# motherboard.net
KiCad netlist of a schematic drawn in EAGLE
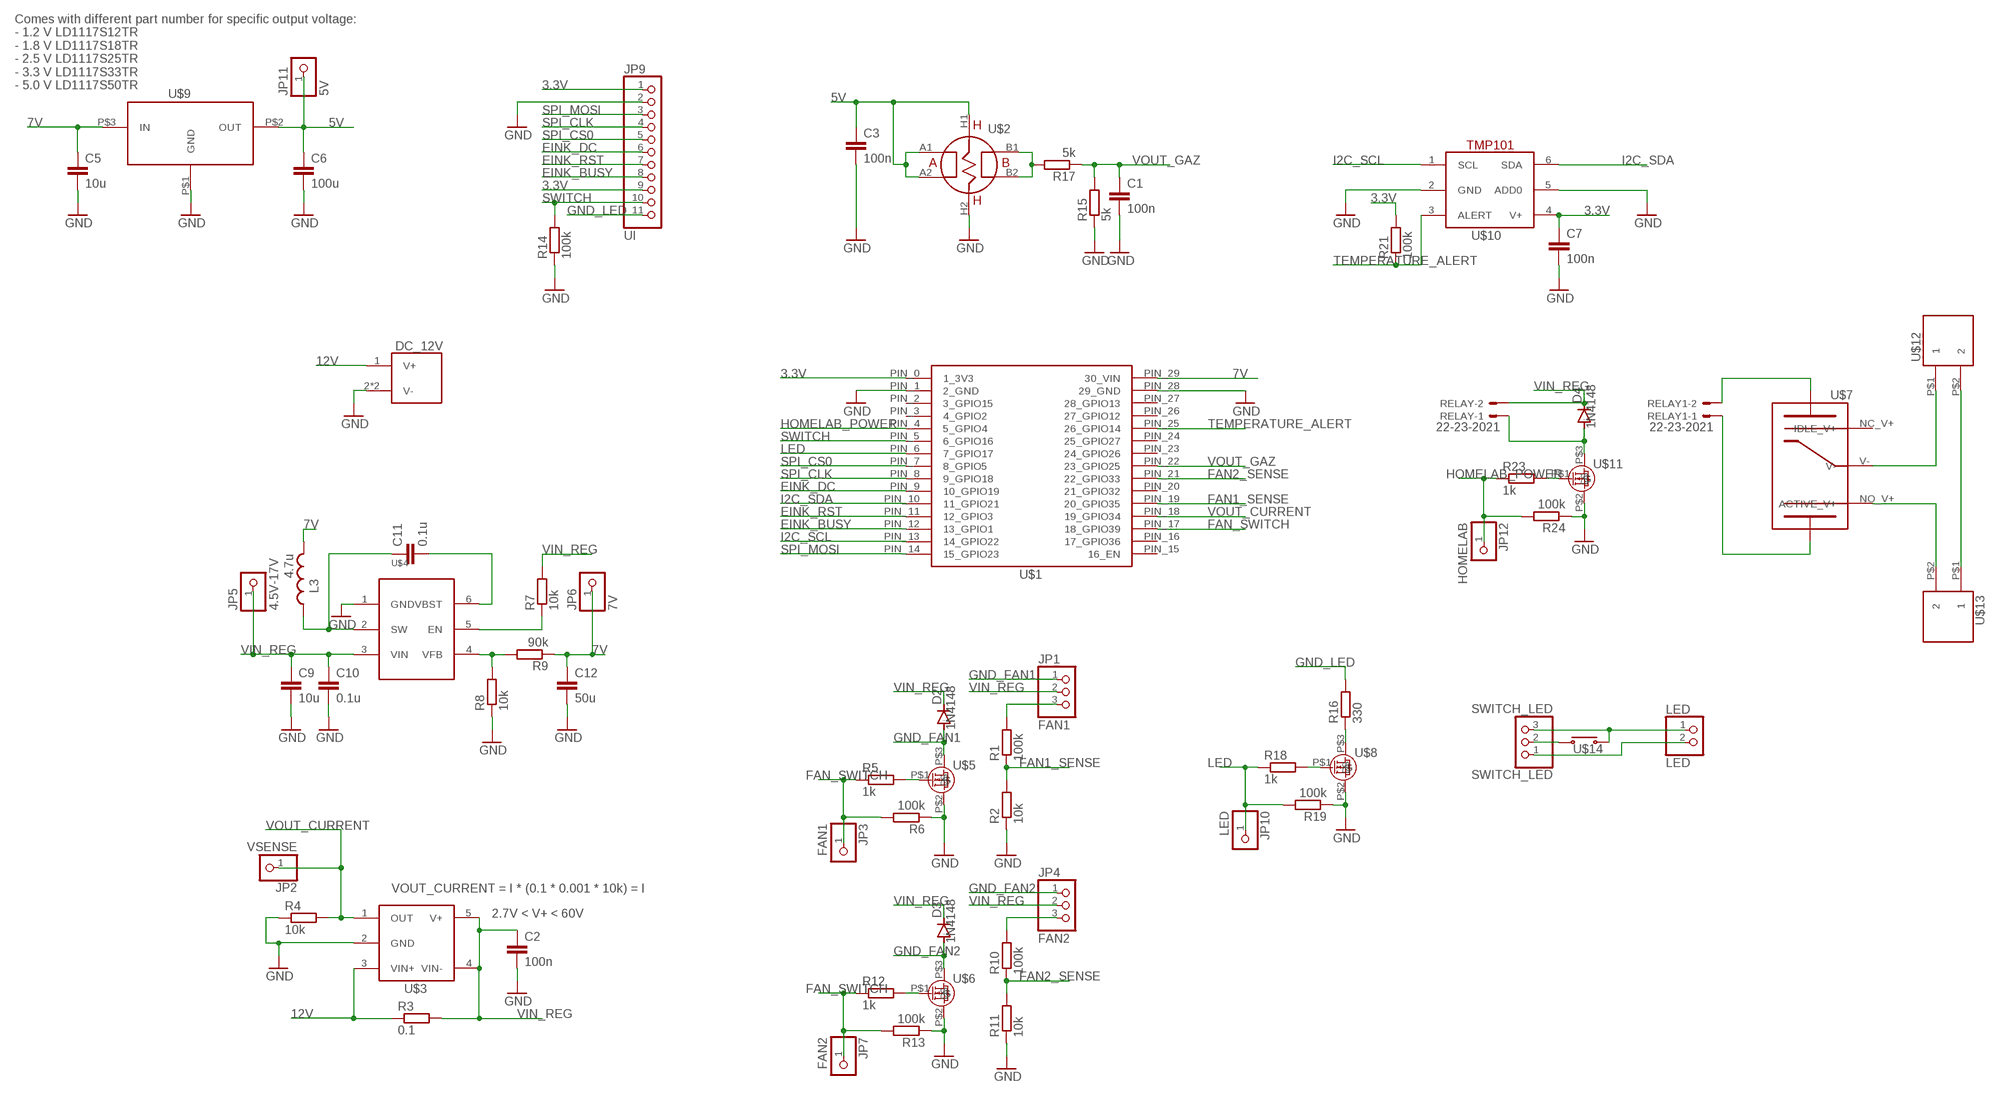
[diagram p0: schematic, sheet 1]

(export (version "E")
  (design (tool "Eeschema 10.0.6"))
  (components
    (comp (ref "C1")
      (value "100n")
      (footprint "eagle-import:C0805")
      (libsource (lib "eagle-import") (part "C-EUC0805"))
    )
    (comp (ref "C2")
      (value "100n")
      (footprint "eagle-import:C0805")
      (libsource (lib "eagle-import") (part "C-EUC0805"))
    )
    (comp (ref "C3")
      (value "100n")
      (footprint "eagle-import:C0805")
      (libsource (lib "eagle-import") (part "C-EUC0805"))
    )
    (comp (ref "C5")
      (value "10u")
      (footprint "eagle-import:C0805")
      (libsource (lib "eagle-import") (part "C-EUC0805"))
    )
    (comp (ref "C6")
      (value "100u")
      (footprint "eagle-import:C0805")
      (libsource (lib "eagle-import") (part "C-EUC0805"))
    )
    (comp (ref "C7")
      (value "100n")
      (footprint "eagle-import:C0805")
      (libsource (lib "eagle-import") (part "C-EUC0805"))
    )
    (comp (ref "C9")
      (value "10u")
      (footprint "eagle-import:C0805")
      (libsource (lib "eagle-import") (part "C-EUC0805"))
    )
    (comp (ref "C10")
      (value "0.1u")
      (footprint "eagle-import:C0805")
      (libsource (lib "eagle-import") (part "C-EUC0805"))
    )
    (comp (ref "C11")
      (value "0.1u")
      (footprint "eagle-import:C0805")
      (libsource (lib "eagle-import") (part "C-EUC0805"))
    )
    (comp (ref "C12")
      (value "50u")
      (footprint "eagle-import:C0805")
      (libsource (lib "eagle-import") (part "C-EUC0805"))
    )
    (comp (ref "D2")
      (value "1N4148")
      (footprint "eagle-import:DO-214AC")
      (libsource (lib "eagle-import") (part "DIODE-DO-214AC"))
    )
    (comp (ref "D3")
      (value "1N4148")
      (footprint "eagle-import:DO-214AC")
      (libsource (lib "eagle-import") (part "DIODE-DO-214AC"))
    )
    (comp (ref "D4")
      (value "1N4148")
      (footprint "eagle-import:DO-214AC")
      (libsource (lib "eagle-import") (part "DIODE-DO-214AC"))
    )
    (comp (ref "DC_12V")
      (value "DC_POWER_2.1MM")
      (footprint "eagle-import:DC_POWER_2.1MM")
      (libsource (lib "eagle-import") (part "DC_POWER_2.1MM"))
    )
    (comp (ref "JP1")
      (value "FAN1")
      (footprint "eagle-import:1X03")
      (libsource (lib "eagle-import") (part "PINHD-1X3"))
    )
    (comp (ref "JP2")
      (value "VSENSE")
      (footprint "eagle-import:1X01")
      (libsource (lib "eagle-import") (part "PINHD-1X1"))
    )
    (comp (ref "JP3")
      (value "FAN1")
      (footprint "eagle-import:1X01")
      (libsource (lib "eagle-import") (part "PINHD-1X1"))
    )
    (comp (ref "JP4")
      (value "FAN2")
      (footprint "eagle-import:1X03")
      (libsource (lib "eagle-import") (part "PINHD-1X3"))
    )
    (comp (ref "JP5")
      (value "4.5V-17V")
      (footprint "eagle-import:1X01")
      (libsource (lib "eagle-import") (part "PINHD-1X1"))
    )
    (comp (ref "JP6")
      (value "7V")
      (footprint "eagle-import:1X01")
      (libsource (lib "eagle-import") (part "PINHD-1X1"))
    )
    (comp (ref "JP7")
      (value "FAN2")
      (footprint "eagle-import:1X01")
      (libsource (lib "eagle-import") (part "PINHD-1X1"))
    )
    (comp (ref "JP9")
      (value "UI")
      (footprint "eagle-import:1X11")
      (libsource (lib "eagle-import") (part "PINHD-1X11"))
    )
    (comp (ref "JP10")
      (value "LED")
      (footprint "eagle-import:1X01")
      (libsource (lib "eagle-import") (part "PINHD-1X1"))
    )
    (comp (ref "JP11")
      (value "5V")
      (footprint "eagle-import:1X01")
      (libsource (lib "eagle-import") (part "PINHD-1X1"))
    )
    (comp (ref "JP12")
      (value "HOMELAB")
      (footprint "eagle-import:1X01")
      (libsource (lib "eagle-import") (part "PINHD-1X1"))
    )
    (comp (ref "L3")
      (value "4.7u")
      (footprint "eagle-import:L3225M")
      (libsource (lib "eagle-import") (part "L-USL3225M"))
    )
    (comp (ref "LED")
      (value "LED")
      (footprint "eagle-import:1X02")
      (libsource (lib "eagle-import") (part "PINHD-1X2"))
    )
    (comp (ref "R1")
      (value "100k")
      (footprint "eagle-import:R0805")
      (libsource (lib "eagle-import") (part "R-EU_R0805"))
    )
    (comp (ref "R2")
      (value "10k")
      (footprint "eagle-import:R0805")
      (libsource (lib "eagle-import") (part "R-EU_R0805"))
    )
    (comp (ref "R3")
      (value "0.1")
      (footprint "eagle-import:R1206")
      (libsource (lib "eagle-import") (part "R-EU_R1206"))
    )
    (comp (ref "R4")
      (value "10k")
      (footprint "eagle-import:R0805")
      (libsource (lib "eagle-import") (part "R-EU_R0805"))
    )
    (comp (ref "R5")
      (value "1k")
      (footprint "eagle-import:R0805")
      (libsource (lib "eagle-import") (part "R-EU_R0805"))
    )
    (comp (ref "R6")
      (value "100k")
      (footprint "eagle-import:R0805")
      (libsource (lib "eagle-import") (part "R-EU_R0805"))
    )
    (comp (ref "R7")
      (value "10k")
      (footprint "eagle-import:R0805")
      (libsource (lib "eagle-import") (part "R-EU_R0805"))
    )
    (comp (ref "R8")
      (value "10k")
      (footprint "eagle-import:R0805")
      (libsource (lib "eagle-import") (part "R-EU_R0805"))
    )
    (comp (ref "R9")
      (value "90k")
      (footprint "eagle-import:R0805")
      (libsource (lib "eagle-import") (part "R-EU_R0805"))
    )
    (comp (ref "R10")
      (value "100k")
      (footprint "eagle-import:R0805")
      (libsource (lib "eagle-import") (part "R-EU_R0805"))
    )
    (comp (ref "R11")
      (value "10k")
      (footprint "eagle-import:R0805")
      (libsource (lib "eagle-import") (part "R-EU_R0805"))
    )
    (comp (ref "R12")
      (value "1k")
      (footprint "eagle-import:R0805")
      (libsource (lib "eagle-import") (part "R-EU_R0805"))
    )
    (comp (ref "R13")
      (value "100k")
      (footprint "eagle-import:R0805")
      (libsource (lib "eagle-import") (part "R-EU_R0805"))
    )
    (comp (ref "R14")
      (value "100k")
      (footprint "eagle-import:R0805")
      (libsource (lib "eagle-import") (part "R-EU_R0805"))
    )
    (comp (ref "R15")
      (value "5k")
      (footprint "eagle-import:R0805")
      (libsource (lib "eagle-import") (part "R-EU_R0805"))
    )
    (comp (ref "R16")
      (value "330")
      (footprint "eagle-import:R0805")
      (libsource (lib "eagle-import") (part "R-EU_R0805"))
    )
    (comp (ref "R17")
      (value "5k")
      (footprint "eagle-import:R0805")
      (libsource (lib "eagle-import") (part "R-EU_R0805"))
    )
    (comp (ref "R18")
      (value "1k")
      (footprint "eagle-import:R0805")
      (libsource (lib "eagle-import") (part "R-EU_R0805"))
    )
    (comp (ref "R19")
      (value "100k")
      (footprint "eagle-import:R0805")
      (libsource (lib "eagle-import") (part "R-EU_R0805"))
    )
    (comp (ref "R21")
      (value "100k")
      (footprint "eagle-import:R0805")
      (libsource (lib "eagle-import") (part "R-EU_R0805"))
    )
    (comp (ref "R23")
      (value "1k")
      (footprint "eagle-import:R0805")
      (libsource (lib "eagle-import") (part "R-EU_R0805"))
    )
    (comp (ref "R24")
      (value "100k")
      (footprint "eagle-import:R0805")
      (libsource (lib "eagle-import") (part "R-EU_R0805"))
    )
    (comp (ref "RELAY")
      (value "22-23-2021")
      (footprint "eagle-import:22-23-2021")
      (fields (field (name "MF") "MOLEX"))
      (libsource (lib "eagle-import") (part "22-23-2021"))
    )
    (comp (ref "RELAY1")
      (value "22-23-2021")
      (footprint "eagle-import:22-23-2021")
      (fields (field (name "MF") "MOLEX"))
      (libsource (lib "eagle-import") (part "22-23-2021"))
    )
    (comp (ref "SWITCH_LED")
      (value "SWITCH_LED")
      (footprint "eagle-import:1X03")
      (libsource (lib "eagle-import") (part "PINHD-1X3"))
    )
    (comp (ref "U$1")
      (value "ESP32_DEVKIT_V1")
      (footprint "eagle-import:ESP32_DEVKIT_V1")
      (libsource (lib "eagle-import") (part "ESP32_DEVKIT_V1"))
    )
    (comp (ref "U$2")
      (value "MQ_2")
      (footprint "eagle-import:MQ_2")
      (libsource (lib "eagle-import") (part "MQ_2"))
    )
    (comp (ref "U$3")
      (value "INA169")
      (footprint "eagle-import:SOT23_5_PIN")
      (libsource (lib "eagle-import") (part "INA169"))
    )
    (comp (ref "U$4")
      (value "TPS561201")
      (footprint "eagle-import:SOT23_6_PIN")
      (libsource (lib "eagle-import") (part "TPS561201"))
    )
    (comp (ref "U$5")
      (value "MGSF1N03L")
      (footprint "eagle-import:SOT23_3_PIN")
      (libsource (lib "eagle-import") (part "MGSF1N03L"))
    )
    (comp (ref "U$6")
      (value "MGSF1N03L")
      (footprint "eagle-import:SOT23_3_PIN")
      (libsource (lib "eagle-import") (part "MGSF1N03L"))
    )
    (comp (ref "U$7")
      (value "RELAY_SONGLE")
      (footprint "eagle-import:RELAY_SONGLE")
      (libsource (lib "eagle-import") (part "RELAY_SONGLE"))
    )
    (comp (ref "U$8")
      (value "MGSF1N03L")
      (footprint "eagle-import:SOT23_3_PIN")
      (libsource (lib "eagle-import") (part "MGSF1N03L"))
    )
    (comp (ref "U$9")
      (value "LD1117")
      (footprint "eagle-import:SOT223_3_PIN")
      (libsource (lib "eagle-import") (part "LD1117"))
    )
    (comp (ref "U$10")
      (value "TMP101")
      (footprint "eagle-import:SOT23_6_PIN")
      (libsource (lib "eagle-import") (part "TMP101"))
    )
    (comp (ref "U$11")
      (value "MGSF1N03L")
      (footprint "eagle-import:SOT23_3_PIN")
      (libsource (lib "eagle-import") (part "MGSF1N03L"))
    )
    (comp (ref "U$12")
      (value "SCREW_TERMINAL")
      (footprint "eagle-import:SCREW_TERMINAL")
      (libsource (lib "eagle-import") (part "SCREW_TERMINAL"))
    )
    (comp (ref "U$13")
      (value "SCREW_TERMINAL")
      (footprint "eagle-import:SCREW_TERMINAL")
      (libsource (lib "eagle-import") (part "SCREW_TERMINAL"))
    )
    (comp (ref "U$14")
      (value "MOMENTARY_SWITCH")
      (footprint "eagle-import:MOMENTARY_SWITCH")
      (libsource (lib "eagle-import") (part "MOMENTARY_SWITCH"))
    )
  )
  (nets
    (net (code "1") (name "/3.3V") (class "Default")
      (node (ref "C7") (pin "1") (pinfunction "1_1") (pintype "passive"))
      (node (ref "JP9") (pin "1") (pinfunction "1_1") (pintype "passive"))
      (node (ref "JP9") (pin "9") (pinfunction "9_9") (pintype "passive"))
      (node (ref "R21") (pin "2") (pinfunction "2_2") (pintype "passive"))
      (node (ref "U$1") (pin "PIN_0") (pinfunction "1_3V3_PIN_0") (pintype "bidirectional"))
      (node (ref "U$10") (pin "4") (pinfunction "V+_4") (pintype "bidirectional"))
    )
    (net (code "2") (name "/5V") (class "Default")
      (node (ref "C3") (pin "1") (pinfunction "1_1") (pintype "passive"))
      (node (ref "C6") (pin "1") (pinfunction "1_1") (pintype "passive"))
      (node (ref "JP11") (pin "1") (pinfunction "1_1") (pintype "passive"))
      (node (ref "U$2") (pin "A1") (pinfunction "A1_A1") (pintype "bidirectional"))
      (node (ref "U$2") (pin "A2") (pinfunction "A2_A2") (pintype "bidirectional"))
      (node (ref "U$2") (pin "H1") (pinfunction "H1_H1") (pintype "bidirectional"))
      (node (ref "U$9") (pin "P$2") (pinfunction "OUT_P$2") (pintype "bidirectional"))
    )
    (net (code "3") (name "/7V") (class "Default")
      (node (ref "C12") (pin "1") (pinfunction "1_1") (pintype "passive"))
      (node (ref "C5") (pin "1") (pinfunction "1_1") (pintype "passive"))
      (node (ref "JP6") (pin "1") (pinfunction "1_1") (pintype "passive"))
      (node (ref "L3") (pin "2") (pinfunction "2_2") (pintype "passive"))
      (node (ref "R9") (pin "1") (pinfunction "1_1") (pintype "passive"))
      (node (ref "U$1") (pin "PIN_29") (pinfunction "30_VIN_PIN_29") (pintype "bidirectional"))
      (node (ref "U$9") (pin "P$3") (pinfunction "IN_P$3") (pintype "bidirectional"))
    )
    (net (code "4") (name "/12V") (class "Default")
      (node (ref "DC_12V") (pin "1") (pinfunction "V+_1") (pintype "bidirectional"))
      (node (ref "R3") (pin "1") (pinfunction "1_1") (pintype "passive"))
      (node (ref "U$3") (pin "3") (pinfunction "VIN+_3") (pintype "bidirectional"))
    )
    (net (code "5") (name "/EINK_BUSY") (class "Default")
      (node (ref "JP9") (pin "8") (pinfunction "8_8") (pintype "passive"))
      (node (ref "U$1") (pin "PIN_12") (pinfunction "13_GPIO1_PIN_12") (pintype "bidirectional"))
    )
    (net (code "6") (name "/EINK_DC") (class "Default")
      (node (ref "JP9") (pin "6") (pinfunction "6_6") (pintype "passive"))
      (node (ref "U$1") (pin "PIN_9") (pinfunction "10_GPIO19_PIN_9") (pintype "bidirectional"))
    )
    (net (code "7") (name "/EINK_RST") (class "Default")
      (node (ref "JP9") (pin "7") (pinfunction "7_7") (pintype "passive"))
      (node (ref "U$1") (pin "PIN_11") (pinfunction "12_GPIO3_PIN_11") (pintype "bidirectional"))
    )
    (net (code "8") (name "/FAN1_SENSE") (class "Default")
      (node (ref "R1") (pin "1") (pinfunction "1_1") (pintype "passive"))
      (node (ref "R2") (pin "2") (pinfunction "2_2") (pintype "passive"))
      (node (ref "U$1") (pin "PIN_19") (pinfunction "20_GPIO35_PIN_19") (pintype "bidirectional"))
    )
    (net (code "9") (name "/FAN2_SENSE") (class "Default")
      (node (ref "R10") (pin "1") (pinfunction "1_1") (pintype "passive"))
      (node (ref "R11") (pin "2") (pinfunction "2_2") (pintype "passive"))
      (node (ref "U$1") (pin "PIN_21") (pinfunction "22_GPIO33_PIN_21") (pintype "bidirectional"))
    )
    (net (code "10") (name "/FAN_SWITCH") (class "Default")
      (node (ref "JP3") (pin "1") (pinfunction "1_1") (pintype "passive"))
      (node (ref "JP7") (pin "1") (pinfunction "1_1") (pintype "passive"))
      (node (ref "R12") (pin "1") (pinfunction "1_1") (pintype "passive"))
      (node (ref "R13") (pin "2") (pinfunction "2_2") (pintype "passive"))
      (node (ref "R5") (pin "1") (pinfunction "1_1") (pintype "passive"))
      (node (ref "R6") (pin "2") (pinfunction "2_2") (pintype "passive"))
      (node (ref "U$1") (pin "PIN_17") (pinfunction "18_GPIO39_PIN_17") (pintype "bidirectional"))
    )
    (net (code "11") (name "/GND_FAN1") (class "Default")
      (node (ref "D2") (pin "A") (pinfunction "A_A") (pintype "passive"))
      (node (ref "JP1") (pin "1") (pinfunction "1_1") (pintype "passive"))
      (node (ref "U$5") (pin "P$3") (pinfunction "D_P$3") (pintype "bidirectional"))
    )
    (net (code "12") (name "/GND_FAN2") (class "Default")
      (node (ref "D3") (pin "A") (pinfunction "A_A") (pintype "passive"))
      (node (ref "JP4") (pin "1") (pinfunction "1_1") (pintype "passive"))
      (node (ref "U$6") (pin "P$3") (pinfunction "D_P$3") (pintype "bidirectional"))
    )
    (net (code "13") (name "/GND_LED") (class "Default")
      (node (ref "JP9") (pin "11") (pinfunction "11_11") (pintype "passive"))
      (node (ref "R16") (pin "2") (pinfunction "2_2") (pintype "passive"))
    )
    (net (code "14") (name "/HOMELAB_POWER") (class "Default")
      (node (ref "JP12") (pin "1") (pinfunction "1_1") (pintype "passive"))
      (node (ref "R23") (pin "1") (pinfunction "1_1") (pintype "passive"))
      (node (ref "R24") (pin "2") (pinfunction "2_2") (pintype "passive"))
      (node (ref "U$1") (pin "PIN_4") (pinfunction "5_GPIO4_PIN_4") (pintype "bidirectional"))
    )
    (net (code "15") (name "/I2C_SCL") (class "Default")
      (node (ref "U$1") (pin "PIN_13") (pinfunction "14_GPIO22_PIN_13") (pintype "bidirectional"))
      (node (ref "U$10") (pin "1") (pinfunction "SCL_1") (pintype "bidirectional"))
    )
    (net (code "16") (name "/I2C_SDA") (class "Default")
      (node (ref "U$1") (pin "PIN_10") (pinfunction "11_GPIO21_PIN_10") (pintype "bidirectional"))
      (node (ref "U$10") (pin "6") (pinfunction "SDA_6") (pintype "bidirectional"))
    )
    (net (code "17") (name "/LED") (class "Default")
      (node (ref "JP10") (pin "1") (pinfunction "1_1") (pintype "passive"))
      (node (ref "R18") (pin "1") (pinfunction "1_1") (pintype "passive"))
      (node (ref "R19") (pin "2") (pinfunction "2_2") (pintype "passive"))
      (node (ref "U$1") (pin "PIN_6") (pinfunction "7_GPIO17_PIN_6") (pintype "bidirectional"))
    )
    (net (code "18") (name "/SPI_CLK") (class "Default")
      (node (ref "JP9") (pin "4") (pinfunction "4_4") (pintype "passive"))
      (node (ref "U$1") (pin "PIN_8") (pinfunction "9_GPIO18_PIN_8") (pintype "bidirectional"))
    )
    (net (code "19") (name "/SPI_CS0") (class "Default")
      (node (ref "JP9") (pin "5") (pinfunction "5_5") (pintype "passive"))
      (node (ref "U$1") (pin "PIN_7") (pinfunction "8_GPIO5_PIN_7") (pintype "bidirectional"))
    )
    (net (code "20") (name "/SPI_MOSI") (class "Default")
      (node (ref "JP9") (pin "3") (pinfunction "3_3") (pintype "passive"))
      (node (ref "U$1") (pin "PIN_14") (pinfunction "15_GPIO23_PIN_14") (pintype "bidirectional"))
    )
    (net (code "21") (name "/SWITCH") (class "Default")
      (node (ref "JP9") (pin "10") (pinfunction "10_10") (pintype "passive"))
      (node (ref "R14") (pin "2") (pinfunction "2_2") (pintype "passive"))
      (node (ref "U$1") (pin "PIN_5") (pinfunction "6_GPIO16_PIN_5") (pintype "bidirectional"))
    )
    (net (code "22") (name "/TEMPERATURE_ALERT") (class "Default")
      (node (ref "R21") (pin "1") (pinfunction "1_1") (pintype "passive"))
      (node (ref "U$1") (pin "PIN_25") (pinfunction "26_GPIO14_PIN_25") (pintype "bidirectional"))
      (node (ref "U$10") (pin "3") (pinfunction "ALERT_3") (pintype "bidirectional"))
    )
    (net (code "23") (name "/VIN_REG") (class "Default")
      (node (ref "C10") (pin "1") (pinfunction "1_1") (pintype "passive"))
      (node (ref "C2") (pin "1") (pinfunction "1_1") (pintype "passive"))
      (node (ref "C9") (pin "1") (pinfunction "1_1") (pintype "passive"))
      (node (ref "D2") (pin "C") (pinfunction "C_C") (pintype "passive"))
      (node (ref "D3") (pin "C") (pinfunction "C_C") (pintype "passive"))
      (node (ref "D4") (pin "C") (pinfunction "C_C") (pintype "passive"))
      (node (ref "JP1") (pin "2") (pinfunction "2_2") (pintype "passive"))
      (node (ref "JP4") (pin "2") (pinfunction "2_2") (pintype "passive"))
      (node (ref "JP5") (pin "1") (pinfunction "1_1") (pintype "passive"))
      (node (ref "R3") (pin "2") (pinfunction "2_2") (pintype "passive"))
      (node (ref "R7") (pin "2") (pinfunction "2_2") (pintype "passive"))
      (node (ref "RELAY") (pin "2") (pinfunction "S_2") (pintype "passive"))
      (node (ref "U$3") (pin "4") (pinfunction "VIN-_4") (pintype "bidirectional"))
      (node (ref "U$3") (pin "5") (pinfunction "V+_5") (pintype "bidirectional"))
      (node (ref "U$4") (pin "3") (pinfunction "VIN_3") (pintype "bidirectional"))
    )
    (net (code "24") (name "/VOUT_CURRENT") (class "Default")
      (node (ref "JP2") (pin "1") (pinfunction "1_1") (pintype "passive"))
      (node (ref "R4") (pin "2") (pinfunction "2_2") (pintype "passive"))
      (node (ref "U$1") (pin "PIN_18") (pinfunction "19_GPIO34_PIN_18") (pintype "bidirectional"))
      (node (ref "U$3") (pin "1") (pinfunction "OUT_1") (pintype "bidirectional"))
    )
    (net (code "25") (name "/VOUT_GAZ") (class "Default")
      (node (ref "C1") (pin "1") (pinfunction "1_1") (pintype "passive"))
      (node (ref "R15") (pin "2") (pinfunction "2_2") (pintype "passive"))
      (node (ref "R17") (pin "1") (pinfunction "1_1") (pintype "passive"))
      (node (ref "U$1") (pin "PIN_22") (pinfunction "23_GPIO25_PIN_22") (pintype "bidirectional"))
    )
    (net (code "26") (name "GND") (class "Default")
      (node (ref "C1") (pin "2") (pinfunction "2_2") (pintype "passive"))
      (node (ref "C10") (pin "2") (pinfunction "2_2") (pintype "passive"))
      (node (ref "C12") (pin "2") (pinfunction "2_2") (pintype "passive"))
      (node (ref "C2") (pin "2") (pinfunction "2_2") (pintype "passive"))
      (node (ref "C3") (pin "2") (pinfunction "2_2") (pintype "passive"))
      (node (ref "C5") (pin "2") (pinfunction "2_2") (pintype "passive"))
      (node (ref "C6") (pin "2") (pinfunction "2_2") (pintype "passive"))
      (node (ref "C7") (pin "2") (pinfunction "2_2") (pintype "passive"))
      (node (ref "C9") (pin "2") (pinfunction "2_2") (pintype "passive"))
      (node (ref "DC_12V") (pin "2") (pinfunction "V-_2") (pintype "bidirectional"))
      (node (ref "DC_12V") (pin "3") (pinfunction "V-_3") (pintype "bidirectional"))
      (node (ref "JP9") (pin "2") (pinfunction "2_2") (pintype "passive"))
      (node (ref "R11") (pin "1") (pinfunction "1_1") (pintype "passive"))
      (node (ref "R13") (pin "1") (pinfunction "1_1") (pintype "passive"))
      (node (ref "R14") (pin "1") (pinfunction "1_1") (pintype "passive"))
      (node (ref "R15") (pin "1") (pinfunction "1_1") (pintype "passive"))
      (node (ref "R19") (pin "1") (pinfunction "1_1") (pintype "passive"))
      (node (ref "R2") (pin "1") (pinfunction "1_1") (pintype "passive"))
      (node (ref "R24") (pin "1") (pinfunction "1_1") (pintype "passive"))
      (node (ref "R4") (pin "1") (pinfunction "1_1") (pintype "passive"))
      (node (ref "R6") (pin "1") (pinfunction "1_1") (pintype "passive"))
      (node (ref "R8") (pin "1") (pinfunction "1_1") (pintype "passive"))
      (node (ref "U$1") (pin "PIN_1") (pinfunction "2_GND_PIN_1") (pintype "bidirectional"))
      (node (ref "U$1") (pin "PIN_28") (pinfunction "29_GND_PIN_28") (pintype "bidirectional"))
      (node (ref "U$10") (pin "2") (pinfunction "GND_2") (pintype "bidirectional"))
      (node (ref "U$10") (pin "5") (pinfunction "ADD0_5") (pintype "bidirectional"))
      (node (ref "U$11") (pin "P$2") (pinfunction "S_P$2") (pintype "bidirectional"))
      (node (ref "U$2") (pin "H2") (pinfunction "H2_H2") (pintype "bidirectional"))
      (node (ref "U$3") (pin "2") (pinfunction "GND_2") (pintype "bidirectional"))
      (node (ref "U$4") (pin "1") (pinfunction "GND_1") (pintype "bidirectional"))
      (node (ref "U$5") (pin "P$2") (pinfunction "S_P$2") (pintype "bidirectional"))
      (node (ref "U$6") (pin "P$2") (pinfunction "S_P$2") (pintype "bidirectional"))
      (node (ref "U$8") (pin "P$2") (pinfunction "S_P$2") (pintype "bidirectional"))
      (node (ref "U$9") (pin "P$1") (pinfunction "GND_P$1") (pintype "bidirectional"))
    )
    (net (code "27") (name "Net-(JP1-Pad3)") (class "Default")
      (node (ref "JP1") (pin "3") (pinfunction "3_3") (pintype "passive"))
      (node (ref "R1") (pin "2") (pinfunction "2_2") (pintype "passive"))
    )
    (net (code "28") (name "Net-(JP4-Pad3)") (class "Default")
      (node (ref "JP4") (pin "3") (pinfunction "3_3") (pintype "passive"))
      (node (ref "R10") (pin "2") (pinfunction "2_2") (pintype "passive"))
    )
    (net (code "29") (name "Net-(LED-Pad1)") (class "Default")
      (node (ref "LED") (pin "1") (pinfunction "1_1") (pintype "passive"))
      (node (ref "SWITCH_LED") (pin "3") (pinfunction "3_3") (pintype "passive"))
      (node (ref "U$14") (pin "B1") (pinfunction "P$2_B1") (pintype "bidirectional"))
      (node (ref "U$14") (pin "B2") (pinfunction "P$2_B2") (pintype "bidirectional"))
    )
    (net (code "30") (name "Net-(LED-Pad2)") (class "Default")
      (node (ref "LED") (pin "2") (pinfunction "2_2") (pintype "passive"))
      (node (ref "SWITCH_LED") (pin "1") (pinfunction "1_1") (pintype "passive"))
    )
    (net (code "31") (name "Net-(R17-Pad2)") (class "Default")
      (node (ref "R17") (pin "2") (pinfunction "2_2") (pintype "passive"))
      (node (ref "U$2") (pin "B1") (pinfunction "B1_B1") (pintype "bidirectional"))
      (node (ref "U$2") (pin "B2") (pinfunction "B2_B2") (pintype "bidirectional"))
    )
    (net (code "32") (name "Net-(RELAY1A-S)") (class "Default")
      (node (ref "RELAY1") (pin "1") (pinfunction "S_1") (pintype "passive"))
      (node (ref "U$7") (pin "COMMAND_V-") (pinfunction "COMMAND_V-_COMMAND_V-") (pintype "bidirectional"))
    )
    (net (code "33") (name "Net-(RELAY1B-S)") (class "Default")
      (node (ref "RELAY1") (pin "2") (pinfunction "S_2") (pintype "passive"))
      (node (ref "U$7") (pin "COMMAND_V+") (pinfunction "COMMAND_V+_COMMAND_V+") (pintype "bidirectional"))
    )
    (net (code "34") (name "Net-(RELAYA-S)") (class "Default")
      (node (ref "D4") (pin "A") (pinfunction "A_A") (pintype "passive"))
      (node (ref "RELAY") (pin "1") (pinfunction "S_1") (pintype "passive"))
      (node (ref "U$11") (pin "P$3") (pinfunction "D_P$3") (pintype "bidirectional"))
    )
    (net (code "35") (name "Net-(SWITCH_LED-Pad2)") (class "Default")
      (node (ref "SWITCH_LED") (pin "2") (pinfunction "2_2") (pintype "passive"))
      (node (ref "U$14") (pin "A1") (pinfunction "P$1_A1") (pintype "bidirectional"))
      (node (ref "U$14") (pin "A2") (pinfunction "P$1_A2") (pintype "bidirectional"))
    )
    (net (code "36") (name "Net-(U$4-EN)") (class "Default")
      (node (ref "R7") (pin "1") (pinfunction "1_1") (pintype "passive"))
      (node (ref "U$4") (pin "5") (pinfunction "EN_5") (pintype "bidirectional"))
    )
    (net (code "37") (name "Net-(U$4-SW)") (class "Default")
      (node (ref "C11") (pin "1") (pinfunction "1_1") (pintype "passive"))
      (node (ref "L3") (pin "1") (pinfunction "1_1") (pintype "passive"))
      (node (ref "U$4") (pin "2") (pinfunction "SW_2") (pintype "bidirectional"))
    )
    (net (code "38") (name "Net-(U$4-VBST)") (class "Default")
      (node (ref "C11") (pin "2") (pinfunction "2_2") (pintype "passive"))
      (node (ref "U$4") (pin "6") (pinfunction "VBST_6") (pintype "bidirectional"))
    )
    (net (code "39") (name "Net-(U$4-VFB)") (class "Default")
      (node (ref "R8") (pin "2") (pinfunction "2_2") (pintype "passive"))
      (node (ref "R9") (pin "2") (pinfunction "2_2") (pintype "passive"))
      (node (ref "U$4") (pin "4") (pinfunction "VFB_4") (pintype "bidirectional"))
    )
    (net (code "40") (name "Net-(U$5-G)") (class "Default")
      (node (ref "R5") (pin "2") (pinfunction "2_2") (pintype "passive"))
      (node (ref "U$5") (pin "P$1") (pinfunction "G_P$1") (pintype "bidirectional"))
    )
    (net (code "41") (name "Net-(U$6-G)") (class "Default")
      (node (ref "R12") (pin "2") (pinfunction "2_2") (pintype "passive"))
      (node (ref "U$6") (pin "P$1") (pinfunction "G_P$1") (pintype "bidirectional"))
    )
    (net (code "42") (name "Net-(U$8-D)") (class "Default")
      (node (ref "R16") (pin "1") (pinfunction "1_1") (pintype "passive"))
      (node (ref "U$8") (pin "P$3") (pinfunction "D_P$3") (pintype "bidirectional"))
    )
    (net (code "43") (name "Net-(U$8-G)") (class "Default")
      (node (ref "R18") (pin "2") (pinfunction "2_2") (pintype "passive"))
      (node (ref "U$8") (pin "P$1") (pinfunction "G_P$1") (pintype "bidirectional"))
    )
    (net (code "44") (name "Net-(U$11-G)") (class "Default")
      (node (ref "R23") (pin "2") (pinfunction "2_2") (pintype "passive"))
      (node (ref "U$11") (pin "P$1") (pinfunction "G_P$1") (pintype "bidirectional"))
    )
    (net (code "45") (name "Net-(U$12-1)") (class "Default")
      (node (ref "U$12") (pin "P$1") (pinfunction "1_P$1") (pintype "bidirectional"))
      (node (ref "U$7") (pin "V-") (pinfunction "V-_V-") (pintype "bidirectional"))
    )
    (net (code "46") (name "Net-(U$12-2)") (class "Default")
      (node (ref "U$12") (pin "P$2") (pinfunction "2_P$2") (pintype "bidirectional"))
      (node (ref "U$13") (pin "P$1") (pinfunction "1_P$1") (pintype "bidirectional"))
    )
    (net (code "47") (name "Net-(U$13-2)") (class "Default")
      (node (ref "U$13") (pin "P$2") (pinfunction "2_P$2") (pintype "bidirectional"))
      (node (ref "U$7") (pin "NO_V+") (pinfunction "ACTIVE_V+_NO_V+") (pintype "bidirectional"))
    )
    (net (code "48") (name "unconnected-(U$1-3_GPIO15-PadPIN_2)") (class "Default")
      (node (ref "U$1") (pin "PIN_2") (pinfunction "3_GPIO15_PIN_2") (pintype "bidirectional"))
    )
    (net (code "49") (name "unconnected-(U$1-4_GPIO2-PadPIN_3)") (class "Default")
      (node (ref "U$1") (pin "PIN_3") (pinfunction "4_GPIO2_PIN_3") (pintype "bidirectional"))
    )
    (net (code "50") (name "unconnected-(U$1-16_EN-PadPIN_15)") (class "Default")
      (node (ref "U$1") (pin "PIN_15") (pinfunction "16_EN_PIN_15") (pintype "bidirectional"))
    )
    (net (code "51") (name "unconnected-(U$1-17_GPIO36-PadPIN_16)") (class "Default")
      (node (ref "U$1") (pin "PIN_16") (pinfunction "17_GPIO36_PIN_16") (pintype "bidirectional"))
    )
    (net (code "52") (name "unconnected-(U$1-21_GPIO32-PadPIN_20)") (class "Default")
      (node (ref "U$1") (pin "PIN_20") (pinfunction "21_GPIO32_PIN_20") (pintype "bidirectional"))
    )
    (net (code "53") (name "unconnected-(U$1-24_GPIO26-PadPIN_23)") (class "Default")
      (node (ref "U$1") (pin "PIN_23") (pinfunction "24_GPIO26_PIN_23") (pintype "bidirectional"))
    )
    (net (code "54") (name "unconnected-(U$1-25_GPIO27-PadPIN_24)") (class "Default")
      (node (ref "U$1") (pin "PIN_24") (pinfunction "25_GPIO27_PIN_24") (pintype "bidirectional"))
    )
    (net (code "55") (name "unconnected-(U$1-27_GPIO12-PadPIN_26)") (class "Default")
      (node (ref "U$1") (pin "PIN_26") (pinfunction "27_GPIO12_PIN_26") (pintype "bidirectional"))
    )
    (net (code "56") (name "unconnected-(U$1-28_GPIO13-PadPIN_27)") (class "Default")
      (node (ref "U$1") (pin "PIN_27") (pinfunction "28_GPIO13_PIN_27") (pintype "bidirectional"))
    )
    (net (code "57") (name "unconnected-(U$7-IDLE_V+-PadNC_V+)") (class "Default")
      (node (ref "U$7") (pin "NC_V+") (pinfunction "IDLE_V+_NC_V+") (pintype "bidirectional"))
    )
  )
)
